# voltage_level_translators_schematic.net
KiCad netlist of a schematic drawn in Altium Designer
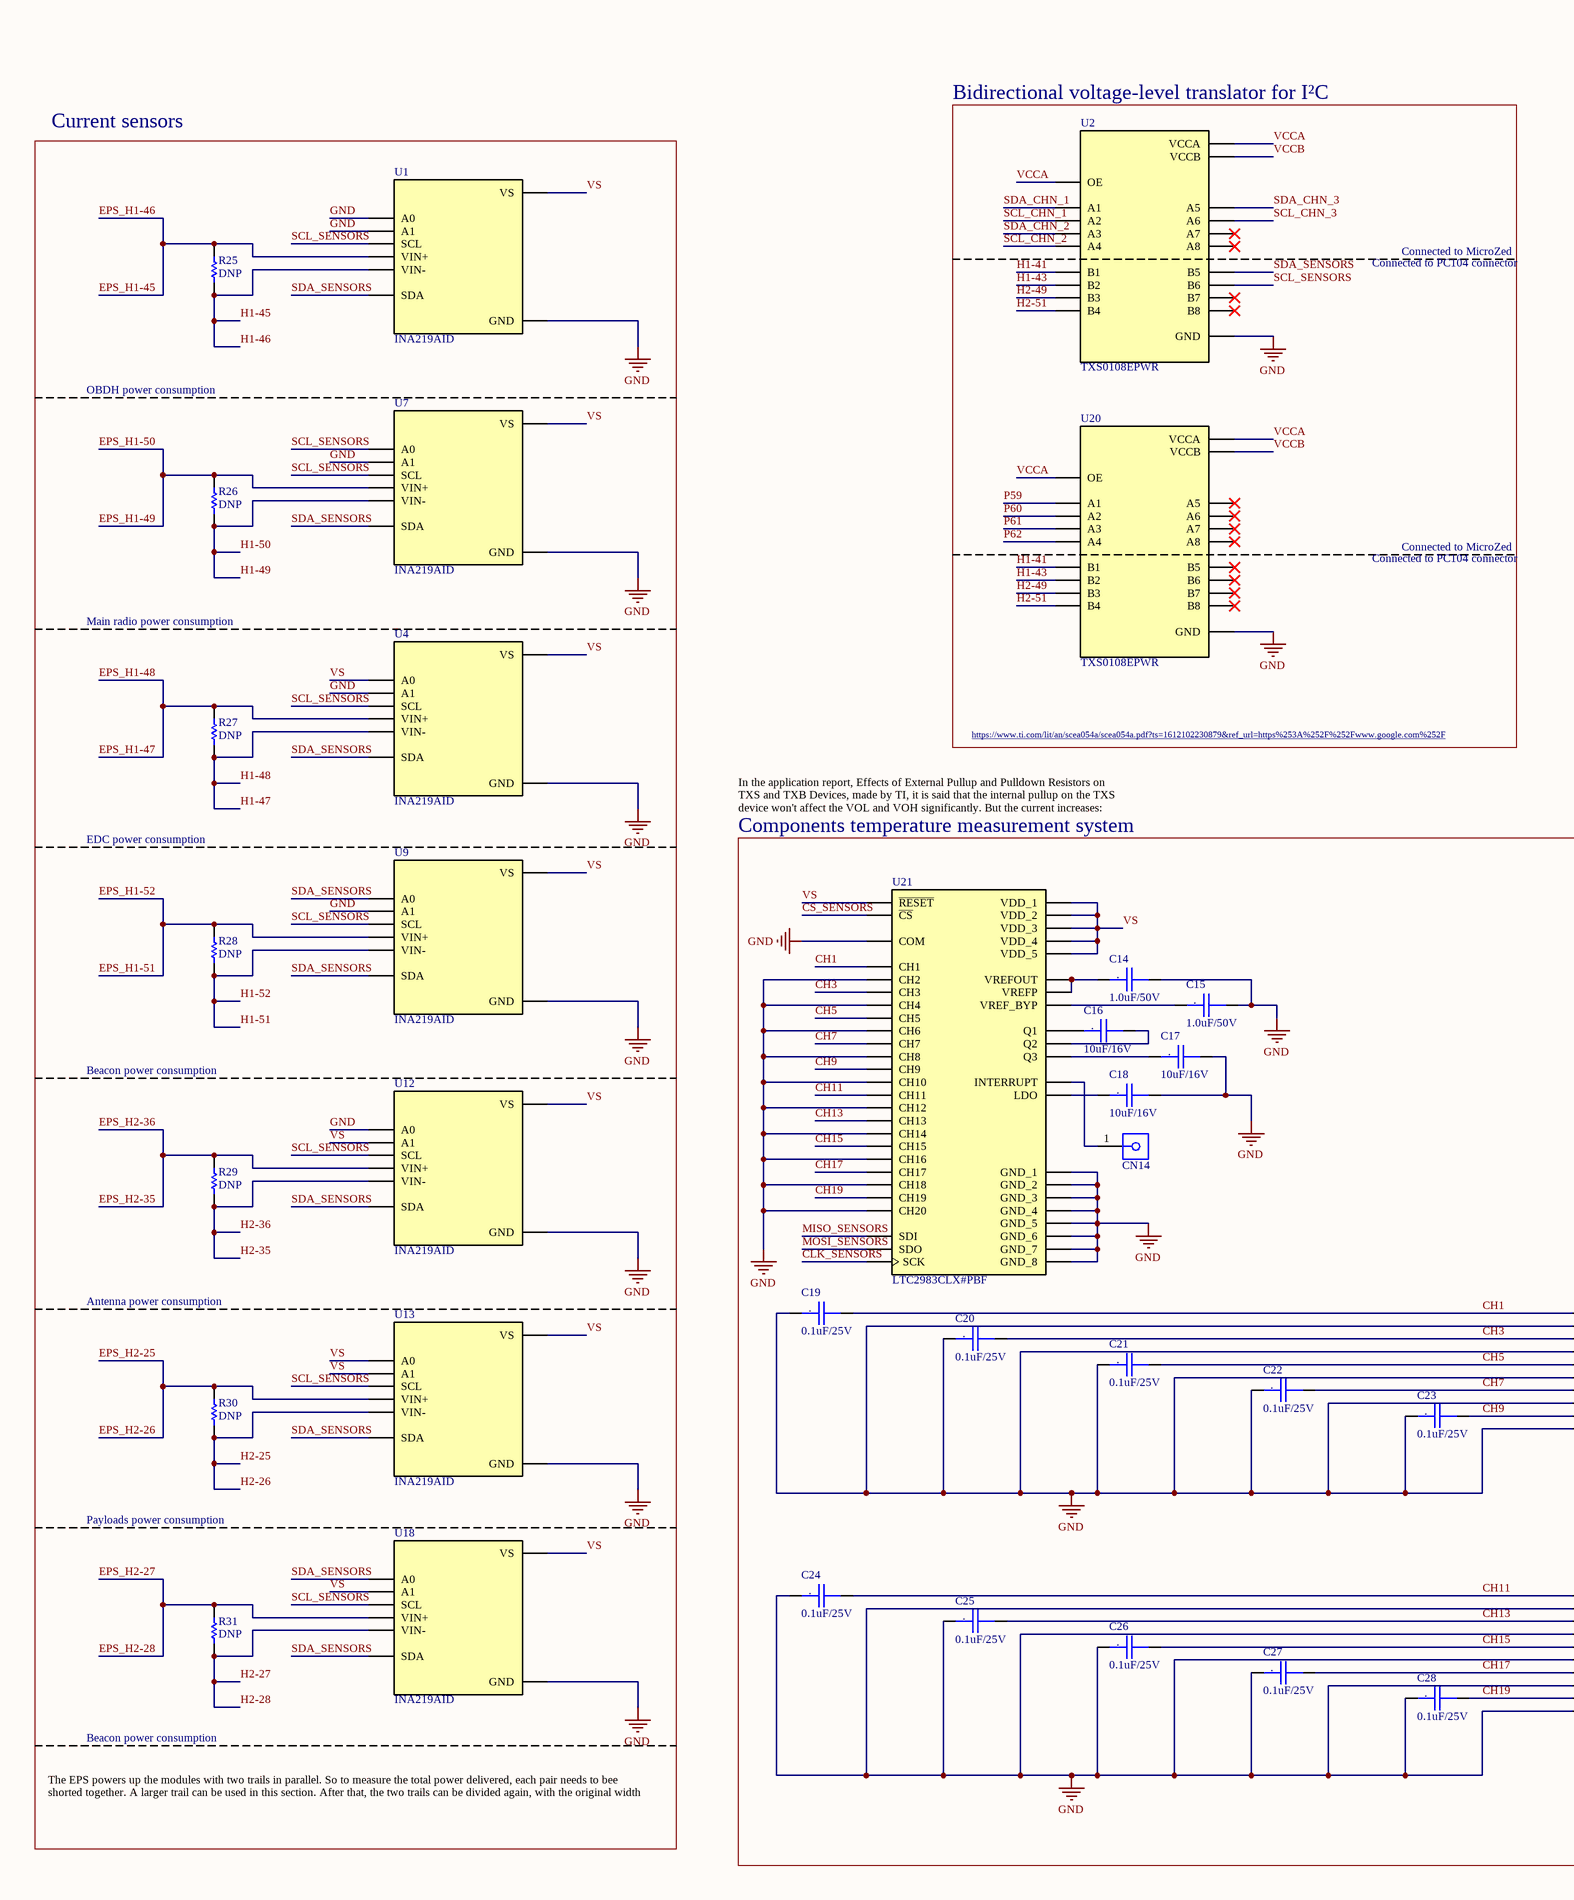
[diagram p0: voltage_level_translators_schematic.SchDoc, left]
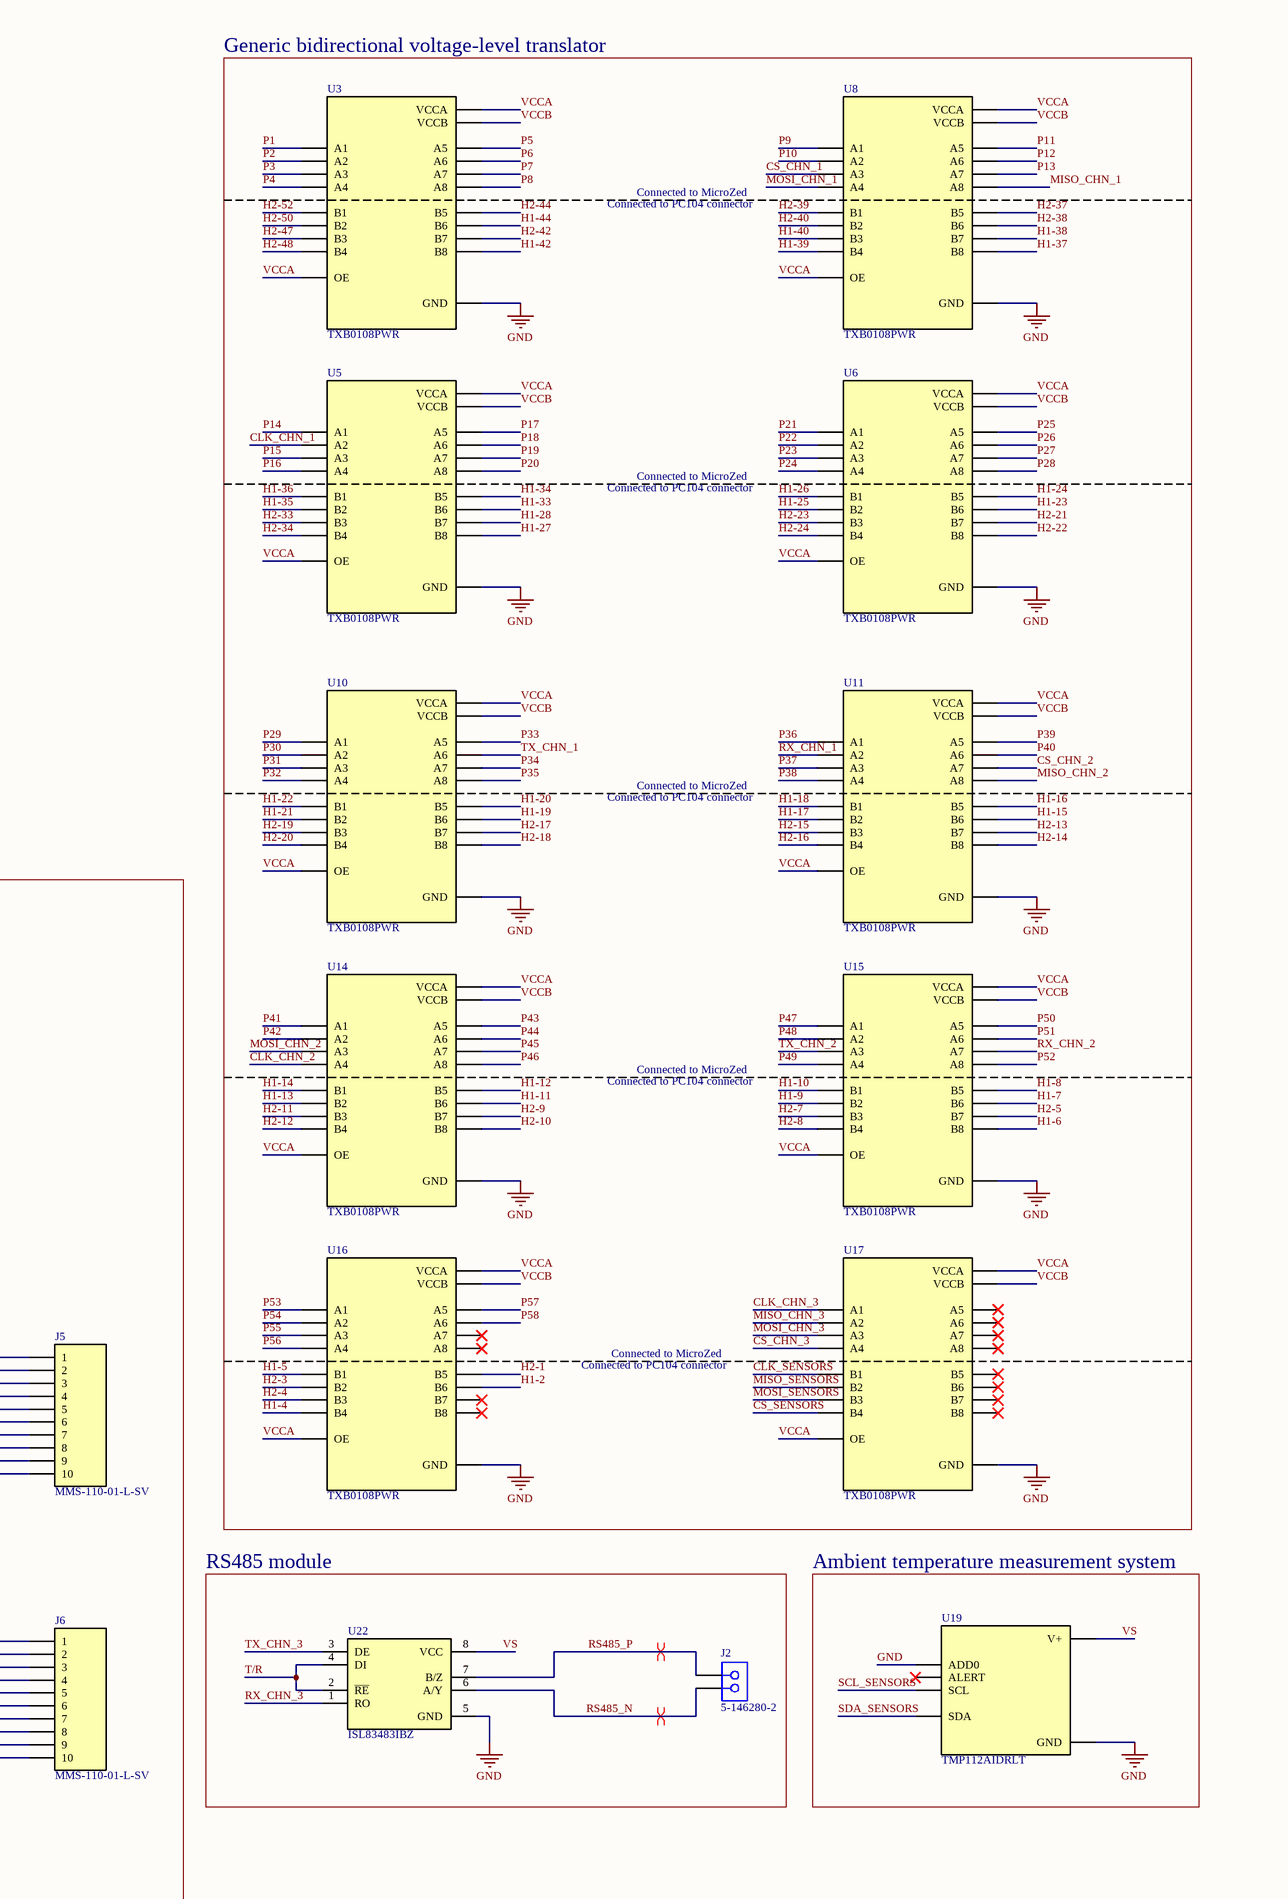
[diagram p1: voltage_level_translators_schematic.SchDoc, right]

(export (version "E")
  (design (tool "Eeschema 10.0.6"))
  (components
    (comp (ref "C14")
      (value "1.0uF/50V")
      (footprint "CC0805")
      (description "CAP CER 1.0uF 50V 10% X7R 0805")
      (fields (field (name "MANUFACTURER PART NUMBER") "C0805X105K5RACAUTO"))
      (libsource (lib "flatsat_platform_2") (part "Cap_Cer_X7R_1.0uF_50V_0805"))
    )
    (comp (ref "C15")
      (value "1.0uF/50V")
      (footprint "CC0805")
      (description "CAP CER 1.0uF 50V 10% X7R 0805")
      (fields (field (name "MANUFACTURER PART NUMBER") "C0805X105K5RACAUTO"))
      (libsource (lib "flatsat_platform_2") (part "Cap_Cer_X7R_1.0uF_50V_0805"))
    )
    (comp (ref "C16")
      (value "10uF/16V")
      (footprint "CC1210")
      (description "CAP CER 10uF 16V 10% X7R 1210")
      (fields (field (name "MANUFACTURER PART NUMBER") "C1210C106K4RACTU"))
      (libsource (lib "flatsat_platform_2") (part "Cap_Cer_X7R_10uF_16V_1210"))
    )
    (comp (ref "C17")
      (value "10uF/16V")
      (footprint "CC1210")
      (description "CAP CER 10uF 16V 10% X7R 1210")
      (fields (field (name "MANUFACTURER PART NUMBER") "C1210C106K4RACTU"))
      (libsource (lib "flatsat_platform_2") (part "Cap_Cer_X7R_10uF_16V_1210"))
    )
    (comp (ref "C18")
      (value "10uF/16V")
      (footprint "CC1210")
      (description "CAP CER 10uF 16V 10% X7R 1210")
      (fields (field (name "MANUFACTURER PART NUMBER") "C1210C106K4RACTU"))
      (libsource (lib "flatsat_platform_2") (part "Cap_Cer_X7R_10uF_16V_1210"))
    )
    (comp (ref "C19")
      (value "0.1uF/25V")
      (footprint "CC0805")
      (description "CAP CER 0.1uF 25V 10% X7R 0805")
      (fields (field (name "MANUFACTURER PART NUMBER") "CC0805KRX7R8BB104"))
      (libsource (lib "flatsat_platform_2") (part "Cap_Cer_X7R_0.1uF_25V_0805"))
    )
    (comp (ref "C20")
      (value "0.1uF/25V")
      (footprint "CC0805")
      (description "CAP CER 0.1uF 25V 10% X7R 0805")
      (fields (field (name "MANUFACTURER PART NUMBER") "CC0805KRX7R8BB104"))
      (libsource (lib "flatsat_platform_2") (part "Cap_Cer_X7R_0.1uF_25V_0805"))
    )
    (comp (ref "C21")
      (value "0.1uF/25V")
      (footprint "CC0805")
      (description "CAP CER 0.1uF 25V 10% X7R 0805")
      (fields (field (name "MANUFACTURER PART NUMBER") "CC0805KRX7R8BB104"))
      (libsource (lib "flatsat_platform_2") (part "Cap_Cer_X7R_0.1uF_25V_0805"))
    )
    (comp (ref "C22")
      (value "0.1uF/25V")
      (footprint "CC0805")
      (description "CAP CER 0.1uF 25V 10% X7R 0805")
      (fields (field (name "MANUFACTURER PART NUMBER") "CC0805KRX7R8BB104"))
      (libsource (lib "flatsat_platform_2") (part "Cap_Cer_X7R_0.1uF_25V_0805"))
    )
    (comp (ref "C23")
      (value "0.1uF/25V")
      (footprint "CC0805")
      (description "CAP CER 0.1uF 25V 10% X7R 0805")
      (fields (field (name "MANUFACTURER PART NUMBER") "CC0805KRX7R8BB104"))
      (libsource (lib "flatsat_platform_2") (part "Cap_Cer_X7R_0.1uF_25V_0805"))
    )
    (comp (ref "C24")
      (value "0.1uF/25V")
      (footprint "CC0805")
      (description "CAP CER 0.1uF 25V 10% X7R 0805")
      (fields (field (name "MANUFACTURER PART NUMBER") "CC0805KRX7R8BB104"))
      (libsource (lib "flatsat_platform_2") (part "Cap_Cer_X7R_0.1uF_25V_0805"))
    )
    (comp (ref "C25")
      (value "0.1uF/25V")
      (footprint "CC0805")
      (description "CAP CER 0.1uF 25V 10% X7R 0805")
      (fields (field (name "MANUFACTURER PART NUMBER") "CC0805KRX7R8BB104"))
      (libsource (lib "flatsat_platform_2") (part "Cap_Cer_X7R_0.1uF_25V_0805"))
    )
    (comp (ref "C26")
      (value "0.1uF/25V")
      (footprint "CC0805")
      (description "CAP CER 0.1uF 25V 10% X7R 0805")
      (fields (field (name "MANUFACTURER PART NUMBER") "CC0805KRX7R8BB104"))
      (libsource (lib "flatsat_platform_2") (part "Cap_Cer_X7R_0.1uF_25V_0805"))
    )
    (comp (ref "C27")
      (value "0.1uF/25V")
      (footprint "CC0805")
      (description "CAP CER 0.1uF 25V 10% X7R 0805")
      (fields (field (name "MANUFACTURER PART NUMBER") "CC0805KRX7R8BB104"))
      (libsource (lib "flatsat_platform_2") (part "Cap_Cer_X7R_0.1uF_25V_0805"))
    )
    (comp (ref "C28")
      (value "0.1uF/25V")
      (footprint "CC0805")
      (description "CAP CER 0.1uF 25V 10% X7R 0805")
      (fields (field (name "MANUFACTURER PART NUMBER") "CC0805KRX7R8BB104"))
      (libsource (lib "flatsat_platform_2") (part "Cap_Cer_X7R_0.1uF_25V_0805"))
    )
    (comp (ref "CN14")
      (value "TSW-101-05-T-S")
      (footprint "PIN BAR 1 2.54mm 180 GRAUS - Hide")
      (description "CONN HEADER 1POS .100\" SNGL TIN")
      (fields (field (name "MANUFACTURER") "Samtec Inc"))
      (libsource (lib "flatsat_platform_2") (part "TSW-101-05-T-S"))
    )
    (comp (ref "J2")
      (value "5-146280-2")
      (footprint "PIN BAR 2 2.54mm 180 GRAUS")
      (description "02 MODII HDR SRST B/A .100CL")
      (fields (field (name "MF") "TE Connectivity"))
      (libsource (lib "flatsat_platform_2") (part "5-146280-2"))
    )
    (comp (ref "J5")
      (value "MMS-110-01-L-SV")
      (footprint "SAMTEC_MMS-110-01-L-SV")
      (description "Conn Socket Strip SKT 10 POS 2mm Solder ST Thru-Hole Tube")
      (libsource (lib "flatsat_platform_2") (part "MMS-110-01-L-SV"))
    )
    (comp (ref "J6")
      (value "MMS-110-01-L-SV")
      (footprint "SAMTEC_MMS-110-01-L-SV")
      (description "Conn Socket Strip SKT 10 POS 2mm Solder ST Thru-Hole Tube")
      (libsource (lib "flatsat_platform_2") (part "MMS-110-01-L-SV"))
    )
    (comp (ref "R25")
      (value "DNP")
      (footprint "0805")
      (description "RES DNP 0805")
      (fields (field (name "MANUFACTURER PART NUMBER") "UR73V2ATTD47L0F"))
      (libsource (lib "flatsat_platform_2") (part "RDNP_0805"))
    )
    (comp (ref "R26")
      (value "DNP")
      (footprint "0805")
      (description "RES DNP 0805")
      (fields (field (name "MANUFACTURER PART NUMBER") "UR73V2ATTD47L0F"))
      (libsource (lib "flatsat_platform_2") (part "RDNP_0805"))
    )
    (comp (ref "R27")
      (value "DNP")
      (footprint "0805")
      (description "RES DNP 0805")
      (fields (field (name "MANUFACTURER PART NUMBER") "UR73V2ATTD47L0F"))
      (libsource (lib "flatsat_platform_2") (part "RDNP_0805"))
    )
    (comp (ref "R28")
      (value "DNP")
      (footprint "0805")
      (description "RES DNP 0805")
      (fields (field (name "MANUFACTURER PART NUMBER") "UR73V2ATTD47L0F"))
      (libsource (lib "flatsat_platform_2") (part "RDNP_0805"))
    )
    (comp (ref "R29")
      (value "DNP")
      (footprint "0805")
      (description "RES DNP 0805")
      (fields (field (name "MANUFACTURER PART NUMBER") "UR73V2ATTD47L0F"))
      (libsource (lib "flatsat_platform_2") (part "RDNP_0805"))
    )
    (comp (ref "R30")
      (value "DNP")
      (footprint "0805")
      (description "RES DNP 0805")
      (fields (field (name "MANUFACTURER PART NUMBER") "UR73V2ATTD47L0F"))
      (libsource (lib "flatsat_platform_2") (part "RDNP_0805"))
    )
    (comp (ref "R31")
      (value "DNP")
      (footprint "0805")
      (description "RES DNP 0805")
      (fields (field (name "MANUFACTURER PART NUMBER") "UR73V2ATTD47L0F"))
      (libsource (lib "flatsat_platform_2") (part "RDNP_0805"))
    )
    (comp (ref "U1")
      (value "INA219AID")
      (footprint "SOIC127P599X175-8N")
      (description "26V, 12-bit, i2c output current/voltage/power monitor 8-SOIC -40 to 125")
      (fields (field (name "MF") "Texas Instruments"))
      (libsource (lib "flatsat_platform_2") (part "INA219AID"))
    )
    (comp (ref "U2")
      (value "TXS0108EPWR")
      (footprint "SOP65P640X120-20N")
      (description "8-Bit Bidirectional Voltage-Level Shifter For Open-Drain And Push-Pull Application")
      (fields (field (name "MF") "Texas Instruments"))
      (libsource (lib "flatsat_platform_2") (part "TXS0108EPWR"))
    )
    (comp (ref "U3")
      (value "TXB0108PWR")
      (footprint "SOP65P640X120-20N")
      (fields (field (name "DIGI-KEY_PART_NUMBER") "296-21527-1-ND") (field (name "MF") "Texas Instruments"))
      (libsource (lib "flatsat_platform_2") (part "TXB0108PWR"))
    )
    (comp (ref "U4")
      (value "INA219AID")
      (footprint "SOIC127P599X175-8N")
      (description "26V, 12-bit, i2c output current/voltage/power monitor 8-SOIC -40 to 125")
      (fields (field (name "MF") "Texas Instruments"))
      (libsource (lib "flatsat_platform_2") (part "INA219AID"))
    )
    (comp (ref "U5")
      (value "TXB0108PWR")
      (footprint "SOP65P640X120-20N")
      (fields (field (name "DIGI-KEY_PART_NUMBER") "296-21527-1-ND") (field (name "MF") "Texas Instruments"))
      (libsource (lib "flatsat_platform_2") (part "TXB0108PWR"))
    )
    (comp (ref "U6")
      (value "TXB0108PWR")
      (footprint "SOP65P640X120-20N")
      (fields (field (name "DIGI-KEY_PART_NUMBER") "296-21527-1-ND") (field (name "MF") "Texas Instruments"))
      (libsource (lib "flatsat_platform_2") (part "TXB0108PWR"))
    )
    (comp (ref "U7")
      (value "INA219AID")
      (footprint "SOIC127P599X175-8N")
      (description "26V, 12-bit, i2c output current/voltage/power monitor 8-SOIC -40 to 125")
      (fields (field (name "MF") "Texas Instruments"))
      (libsource (lib "flatsat_platform_2") (part "INA219AID"))
    )
    (comp (ref "U8")
      (value "TXB0108PWR")
      (footprint "SOP65P640X120-20N")
      (fields (field (name "DIGI-KEY_PART_NUMBER") "296-21527-1-ND") (field (name "MF") "Texas Instruments"))
      (libsource (lib "flatsat_platform_2") (part "TXB0108PWR"))
    )
    (comp (ref "U9")
      (value "INA219AID")
      (footprint "SOIC127P599X175-8N")
      (description "26V, 12-bit, i2c output current/voltage/power monitor 8-SOIC -40 to 125")
      (fields (field (name "MF") "Texas Instruments"))
      (libsource (lib "flatsat_platform_2") (part "INA219AID"))
    )
    (comp (ref "U10")
      (value "TXB0108PWR")
      (footprint "SOP65P640X120-20N")
      (fields (field (name "DIGI-KEY_PART_NUMBER") "296-21527-1-ND") (field (name "MF") "Texas Instruments"))
      (libsource (lib "flatsat_platform_2") (part "TXB0108PWR"))
    )
    (comp (ref "U11")
      (value "TXB0108PWR")
      (footprint "SOP65P640X120-20N")
      (fields (field (name "DIGI-KEY_PART_NUMBER") "296-21527-1-ND") (field (name "MF") "Texas Instruments"))
      (libsource (lib "flatsat_platform_2") (part "TXB0108PWR"))
    )
    (comp (ref "U12")
      (value "INA219AID")
      (footprint "SOIC127P599X175-8N")
      (description "26V, 12-bit, i2c output current/voltage/power monitor 8-SOIC -40 to 125")
      (fields (field (name "MF") "Texas Instruments"))
      (libsource (lib "flatsat_platform_2") (part "INA219AID"))
    )
    (comp (ref "U13")
      (value "INA219AID")
      (footprint "SOIC127P599X175-8N")
      (description "26V, 12-bit, i2c output current/voltage/power monitor 8-SOIC -40 to 125")
      (fields (field (name "MF") "Texas Instruments"))
      (libsource (lib "flatsat_platform_2") (part "INA219AID"))
    )
    (comp (ref "U14")
      (value "TXB0108PWR")
      (footprint "SOP65P640X120-20N")
      (fields (field (name "DIGI-KEY_PART_NUMBER") "296-21527-1-ND") (field (name "MF") "Texas Instruments"))
      (libsource (lib "flatsat_platform_2") (part "TXB0108PWR"))
    )
    (comp (ref "U15")
      (value "TXB0108PWR")
      (footprint "SOP65P640X120-20N")
      (fields (field (name "DIGI-KEY_PART_NUMBER") "296-21527-1-ND") (field (name "MF") "Texas Instruments"))
      (libsource (lib "flatsat_platform_2") (part "TXB0108PWR"))
    )
    (comp (ref "U16")
      (value "TXB0108PWR")
      (footprint "SOP65P640X120-20N")
      (fields (field (name "DIGI-KEY_PART_NUMBER") "296-21527-1-ND") (field (name "MF") "Texas Instruments"))
      (libsource (lib "flatsat_platform_2") (part "TXB0108PWR"))
    )
    (comp (ref "U17")
      (value "TXB0108PWR")
      (footprint "SOP65P640X120-20N")
      (fields (field (name "DIGI-KEY_PART_NUMBER") "296-21527-1-ND") (field (name "MF") "Texas Instruments"))
      (libsource (lib "flatsat_platform_2") (part "TXB0108PWR"))
    )
    (comp (ref "U18")
      (value "INA219AID")
      (footprint "SOIC127P599X175-8N")
      (description "26V, 12-bit, i2c output current/voltage/power monitor 8-SOIC -40 to 125")
      (fields (field (name "MF") "Texas Instruments"))
      (libsource (lib "flatsat_platform_2") (part "INA219AID"))
    )
    (comp (ref "U19")
      (value "TMP112AIDRLT")
      (footprint "SOT50P160X60-6N")
      (fields (field (name "MF") "Texas Instruments"))
      (libsource (lib "flatsat_platform_2") (part "TMP112AIDRLT"))
    )
    (comp (ref "U20")
      (value "TXS0108EPWR")
      (footprint "SOP65P640X120-20N")
      (description "8-Bit Bidirectional Voltage-Level Shifter For Open-Drain And Push-Pull Application")
      (fields (field (name "MF") "Texas Instruments"))
      (libsource (lib "flatsat_platform_2") (part "TXS0108EPWR"))
    )
    (comp (ref "U21")
      (value "LTC2983CLX#PBF")
      (footprint "QFP50P900X900X160-48N")
      (description "IC SENSOR THERMAL")
      (fields (field (name "MF") "Analog Devices"))
      (libsource (lib "flatsat_platform_2") (part "LTC2983CLX#PBF"))
    )
    (comp (ref "U22")
      (value "ISL83483IBZ")
      (footprint "SOIC127P600X175-8N")
      (description "1/1 Transceiver Half RS422, RS485 8-SOIC")
      (fields
        (field (name "MF") "Renesas Electronics")
        (field (name "MANUFACTURER PART NUMBER") "ISL83483IBZ-T")
      )
      (libsource (lib "flatsat_platform_2") (part "ISL83483IBZ"))
    )
  )
  (nets
    (net (code "1") (name "/CH1") (class "Default")
      (node (ref "C19") (pin "2") (pinfunction "2_2") (pintype "passive"))
      (node (ref "J5") (pin "1") (pinfunction "1_1") (pintype "passive"))
      (node (ref "U21") (pin "16") (pinfunction "CH1_16") (pintype "power_in"))
    )
    (net (code "2") (name "/CH3") (class "Default")
      (node (ref "C20") (pin "2") (pinfunction "2_2") (pintype "passive"))
      (node (ref "J5") (pin "3") (pinfunction "3_3") (pintype "passive"))
      (node (ref "U21") (pin "18") (pinfunction "CH3_18") (pintype "power_in"))
    )
    (net (code "3") (name "/CH5") (class "Default")
      (node (ref "C21") (pin "2") (pinfunction "2_2") (pintype "passive"))
      (node (ref "J5") (pin "5") (pinfunction "5_5") (pintype "passive"))
      (node (ref "U21") (pin "20") (pinfunction "CH5_20") (pintype "power_in"))
    )
    (net (code "4") (name "/CH7") (class "Default")
      (node (ref "C22") (pin "2") (pinfunction "2_2") (pintype "passive"))
      (node (ref "J5") (pin "7") (pinfunction "7_7") (pintype "passive"))
      (node (ref "U21") (pin "22") (pinfunction "CH7_22") (pintype "power_in"))
    )
    (net (code "5") (name "/CH9") (class "Default")
      (node (ref "C23") (pin "2") (pinfunction "2_2") (pintype "passive"))
      (node (ref "J5") (pin "9") (pinfunction "9_9") (pintype "passive"))
      (node (ref "U21") (pin "24") (pinfunction "CH9_24") (pintype "power_in"))
    )
    (net (code "6") (name "/CH11") (class "Default")
      (node (ref "C24") (pin "2") (pinfunction "2_2") (pintype "passive"))
      (node (ref "J6") (pin "1") (pinfunction "1_1") (pintype "passive"))
      (node (ref "U21") (pin "26") (pinfunction "CH11_26") (pintype "power_in"))
    )
    (net (code "7") (name "/CH13") (class "Default")
      (node (ref "C25") (pin "2") (pinfunction "2_2") (pintype "passive"))
      (node (ref "J6") (pin "3") (pinfunction "3_3") (pintype "passive"))
      (node (ref "U21") (pin "28") (pinfunction "CH13_28") (pintype "power_in"))
    )
    (net (code "8") (name "/CH15") (class "Default")
      (node (ref "C26") (pin "2") (pinfunction "2_2") (pintype "passive"))
      (node (ref "J6") (pin "5") (pinfunction "5_5") (pintype "passive"))
      (node (ref "U21") (pin "30") (pinfunction "CH15_30") (pintype "power_in"))
    )
    (net (code "9") (name "/CH17") (class "Default")
      (node (ref "C27") (pin "2") (pinfunction "2_2") (pintype "passive"))
      (node (ref "J6") (pin "7") (pinfunction "7_7") (pintype "passive"))
      (node (ref "U21") (pin "32") (pinfunction "CH17_32") (pintype "power_in"))
    )
    (net (code "10") (name "/CH19") (class "Default")
      (node (ref "C28") (pin "2") (pinfunction "2_2") (pintype "passive"))
      (node (ref "J6") (pin "9") (pinfunction "9_9") (pintype "passive"))
      (node (ref "U21") (pin "34") (pinfunction "CH19_34") (pintype "power_in"))
    )
    (net (code "11") (name "/CLK_CHN_1") (class "Default")
      (node (ref "U5") (pin "3") (pinfunction "A2_3") (pintype "power_in"))
    )
    (net (code "12") (name "/CLK_CHN_2") (class "Default")
      (node (ref "U14") (pin "5") (pinfunction "A4_5") (pintype "power_in"))
    )
    (net (code "13") (name "/CLK_CHN_3") (class "Default")
      (node (ref "U17") (pin "1") (pinfunction "A1_1") (pintype "power_in"))
    )
    (net (code "14") (name "/CLK_SENSORS") (class "Default")
      (node (ref "U17") (pin "20") (pinfunction "B1_20") (pintype "power_in"))
      (node (ref "U21") (pin "38") (pinfunction "SCK_38") (pintype "power_in"))
    )
    (net (code "15") (name "/CS_CHN_1") (class "Default")
      (node (ref "U8") (pin "4") (pinfunction "A3_4") (pintype "power_in"))
    )
    (net (code "16") (name "/CS_CHN_2") (class "Default")
      (node (ref "U11") (pin "8") (pinfunction "A7_8") (pintype "power_in"))
    )
    (net (code "17") (name "/CS_CHN_3") (class "Default")
      (node (ref "U17") (pin "5") (pinfunction "A4_5") (pintype "power_in"))
    )
    (net (code "18") (name "/CS_SENSORS") (class "Default")
      (node (ref "U17") (pin "16") (pinfunction "B4_16") (pintype "power_in"))
      (node (ref "U21") (pin "41") (pinfunction "~{CS}_41") (pintype "power_in"))
    )
    (net (code "19") (name "/EPS_H1-45") (class "Default")
      (node (ref "R25") (pin "1") (pinfunction "1_1") (pintype "passive"))
      (node (ref "U1") (pin "8") (pinfunction "VIN+_8") (pintype "power_in"))
    )
    (net (code "20") (name "/EPS_H1-47") (class "Default")
      (node (ref "R27") (pin "1") (pinfunction "1_1") (pintype "passive"))
      (node (ref "U4") (pin "8") (pinfunction "VIN+_8") (pintype "power_in"))
    )
    (net (code "21") (name "/EPS_H1-49") (class "Default")
      (node (ref "R26") (pin "1") (pinfunction "1_1") (pintype "passive"))
      (node (ref "U7") (pin "8") (pinfunction "VIN+_8") (pintype "power_in"))
    )
    (net (code "22") (name "/EPS_H1-51") (class "Default")
      (node (ref "R28") (pin "1") (pinfunction "1_1") (pintype "passive"))
      (node (ref "U9") (pin "8") (pinfunction "VIN+_8") (pintype "power_in"))
    )
    (net (code "23") (name "/EPS_H2-25") (class "Default")
      (node (ref "R30") (pin "1") (pinfunction "1_1") (pintype "passive"))
      (node (ref "U13") (pin "8") (pinfunction "VIN+_8") (pintype "power_in"))
    )
    (net (code "24") (name "/EPS_H2-27") (class "Default")
      (node (ref "R31") (pin "1") (pinfunction "1_1") (pintype "passive"))
      (node (ref "U18") (pin "8") (pinfunction "VIN+_8") (pintype "power_in"))
    )
    (net (code "25") (name "/EPS_H2-35") (class "Default")
      (node (ref "R29") (pin "1") (pinfunction "1_1") (pintype "passive"))
      (node (ref "U12") (pin "8") (pinfunction "VIN+_8") (pintype "power_in"))
    )
    (net (code "26") (name "/H1-2") (class "Default")
      (node (ref "U16") (pin "14") (pinfunction "B6_14") (pintype "power_in"))
    )
    (net (code "27") (name "/H1-4") (class "Default")
      (node (ref "U16") (pin "16") (pinfunction "B4_16") (pintype "power_in"))
    )
    (net (code "28") (name "/H1-5") (class "Default")
      (node (ref "U16") (pin "20") (pinfunction "B1_20") (pintype "power_in"))
    )
    (net (code "29") (name "/H1-6") (class "Default")
      (node (ref "U15") (pin "12") (pinfunction "B8_12") (pintype "power_in"))
    )
    (net (code "30") (name "/H1-7") (class "Default")
      (node (ref "U15") (pin "14") (pinfunction "B6_14") (pintype "power_in"))
    )
    (net (code "31") (name "/H1-8") (class "Default")
      (node (ref "U15") (pin "15") (pinfunction "B5_15") (pintype "power_in"))
    )
    (net (code "32") (name "/H1-9") (class "Default")
      (node (ref "U15") (pin "18") (pinfunction "B2_18") (pintype "power_in"))
    )
    (net (code "33") (name "/H1-10") (class "Default")
      (node (ref "U15") (pin "20") (pinfunction "B1_20") (pintype "power_in"))
    )
    (net (code "34") (name "/H1-11") (class "Default")
      (node (ref "U14") (pin "14") (pinfunction "B6_14") (pintype "power_in"))
    )
    (net (code "35") (name "/H1-12") (class "Default")
      (node (ref "U14") (pin "15") (pinfunction "B5_15") (pintype "power_in"))
    )
    (net (code "36") (name "/H1-13") (class "Default")
      (node (ref "U14") (pin "18") (pinfunction "B2_18") (pintype "power_in"))
    )
    (net (code "37") (name "/H1-14") (class "Default")
      (node (ref "U14") (pin "20") (pinfunction "B1_20") (pintype "power_in"))
    )
    (net (code "38") (name "/H1-15") (class "Default")
      (node (ref "U11") (pin "14") (pinfunction "B6_14") (pintype "power_in"))
    )
    (net (code "39") (name "/H1-16") (class "Default")
      (node (ref "U11") (pin "15") (pinfunction "B5_15") (pintype "power_in"))
    )
    (net (code "40") (name "/H1-17") (class "Default")
      (node (ref "U11") (pin "18") (pinfunction "B2_18") (pintype "power_in"))
    )
    (net (code "41") (name "/H1-18") (class "Default")
      (node (ref "U11") (pin "20") (pinfunction "B1_20") (pintype "power_in"))
    )
    (net (code "42") (name "/H1-19") (class "Default")
      (node (ref "U10") (pin "14") (pinfunction "B6_14") (pintype "power_in"))
    )
    (net (code "43") (name "/H1-20") (class "Default")
      (node (ref "U10") (pin "15") (pinfunction "B5_15") (pintype "power_in"))
    )
    (net (code "44") (name "/H1-21") (class "Default")
      (node (ref "U10") (pin "18") (pinfunction "B2_18") (pintype "power_in"))
    )
    (net (code "45") (name "/H1-22") (class "Default")
      (node (ref "U10") (pin "20") (pinfunction "B1_20") (pintype "power_in"))
    )
    (net (code "46") (name "/H1-23") (class "Default")
      (node (ref "U6") (pin "14") (pinfunction "B6_14") (pintype "power_in"))
    )
    (net (code "47") (name "/H1-24") (class "Default")
      (node (ref "U6") (pin "15") (pinfunction "B5_15") (pintype "power_in"))
    )
    (net (code "48") (name "/H1-25") (class "Default")
      (node (ref "U6") (pin "18") (pinfunction "B2_18") (pintype "power_in"))
    )
    (net (code "49") (name "/H1-26") (class "Default")
      (node (ref "U6") (pin "20") (pinfunction "B1_20") (pintype "power_in"))
    )
    (net (code "50") (name "/H1-27") (class "Default")
      (node (ref "U5") (pin "12") (pinfunction "B8_12") (pintype "power_in"))
    )
    (net (code "51") (name "/H1-28") (class "Default")
      (node (ref "U5") (pin "13") (pinfunction "B7_13") (pintype "power_in"))
    )
    (net (code "52") (name "/H1-33") (class "Default")
      (node (ref "U5") (pin "14") (pinfunction "B6_14") (pintype "power_in"))
    )
    (net (code "53") (name "/H1-34") (class "Default")
      (node (ref "U5") (pin "15") (pinfunction "B5_15") (pintype "power_in"))
    )
    (net (code "54") (name "/H1-35") (class "Default")
      (node (ref "U5") (pin "18") (pinfunction "B2_18") (pintype "power_in"))
    )
    (net (code "55") (name "/H1-36") (class "Default")
      (node (ref "U5") (pin "20") (pinfunction "B1_20") (pintype "power_in"))
    )
    (net (code "56") (name "/H1-37") (class "Default")
      (node (ref "U8") (pin "12") (pinfunction "B8_12") (pintype "power_in"))
    )
    (net (code "57") (name "/H1-38") (class "Default")
      (node (ref "U8") (pin "13") (pinfunction "B7_13") (pintype "power_in"))
    )
    (net (code "58") (name "/H1-39") (class "Default")
      (node (ref "U8") (pin "16") (pinfunction "B4_16") (pintype "power_in"))
    )
    (net (code "59") (name "/H1-40") (class "Default")
      (node (ref "U8") (pin "17") (pinfunction "B3_17") (pintype "power_in"))
    )
    (net (code "60") (name "/H1-41") (class "Default")
      (node (ref "U2") (pin "20") (pinfunction "B1_20") (pintype "power_in"))
      (node (ref "U20") (pin "20") (pinfunction "B1_20") (pintype "power_in"))
    )
    (net (code "61") (name "/H1-42") (class "Default")
      (node (ref "U3") (pin "12") (pinfunction "B8_12") (pintype "power_in"))
    )
    (net (code "62") (name "/H1-43") (class "Default")
      (node (ref "U2") (pin "18") (pinfunction "B2_18") (pintype "power_in"))
      (node (ref "U20") (pin "18") (pinfunction "B2_18") (pintype "power_in"))
    )
    (net (code "63") (name "/H1-44") (class "Default")
      (node (ref "U3") (pin "14") (pinfunction "B6_14") (pintype "power_in"))
    )
    (net (code "64") (name "/H1-45") (class "Default")
      (node (ref "R25") (pin "2") (pinfunction "2_2") (pintype "passive"))
      (node (ref "U1") (pin "7") (pinfunction "VIN-_7") (pintype "power_in"))
    )
    (net (code "65") (name "/H1-47") (class "Default")
      (node (ref "R27") (pin "2") (pinfunction "2_2") (pintype "passive"))
      (node (ref "U4") (pin "7") (pinfunction "VIN-_7") (pintype "power_in"))
    )
    (net (code "66") (name "/H1-49") (class "Default")
      (node (ref "R26") (pin "2") (pinfunction "2_2") (pintype "passive"))
      (node (ref "U7") (pin "7") (pinfunction "VIN-_7") (pintype "power_in"))
    )
    (net (code "67") (name "/H1-51") (class "Default")
      (node (ref "R28") (pin "2") (pinfunction "2_2") (pintype "passive"))
      (node (ref "U9") (pin "7") (pinfunction "VIN-_7") (pintype "power_in"))
    )
    (net (code "68") (name "/H2-1") (class "Default")
      (node (ref "U16") (pin "15") (pinfunction "B5_15") (pintype "power_in"))
    )
    (net (code "69") (name "/H2-3") (class "Default")
      (node (ref "U16") (pin "18") (pinfunction "B2_18") (pintype "power_in"))
    )
    (net (code "70") (name "/H2-4") (class "Default")
      (node (ref "U16") (pin "17") (pinfunction "B3_17") (pintype "power_in"))
    )
    (net (code "71") (name "/H2-5") (class "Default")
      (node (ref "U15") (pin "13") (pinfunction "B7_13") (pintype "power_in"))
    )
    (net (code "72") (name "/H2-7") (class "Default")
      (node (ref "U15") (pin "17") (pinfunction "B3_17") (pintype "power_in"))
    )
    (net (code "73") (name "/H2-8") (class "Default")
      (node (ref "U15") (pin "16") (pinfunction "B4_16") (pintype "power_in"))
    )
    (net (code "74") (name "/H2-9") (class "Default")
      (node (ref "U14") (pin "13") (pinfunction "B7_13") (pintype "power_in"))
    )
    (net (code "75") (name "/H2-10") (class "Default")
      (node (ref "U14") (pin "12") (pinfunction "B8_12") (pintype "power_in"))
    )
    (net (code "76") (name "/H2-11") (class "Default")
      (node (ref "U14") (pin "17") (pinfunction "B3_17") (pintype "power_in"))
    )
    (net (code "77") (name "/H2-12") (class "Default")
      (node (ref "U14") (pin "16") (pinfunction "B4_16") (pintype "power_in"))
    )
    (net (code "78") (name "/H2-13") (class "Default")
      (node (ref "U11") (pin "13") (pinfunction "B7_13") (pintype "power_in"))
    )
    (net (code "79") (name "/H2-14") (class "Default")
      (node (ref "U11") (pin "12") (pinfunction "B8_12") (pintype "power_in"))
    )
    (net (code "80") (name "/H2-15") (class "Default")
      (node (ref "U11") (pin "17") (pinfunction "B3_17") (pintype "power_in"))
    )
    (net (code "81") (name "/H2-16") (class "Default")
      (node (ref "U11") (pin "16") (pinfunction "B4_16") (pintype "power_in"))
    )
    (net (code "82") (name "/H2-17") (class "Default")
      (node (ref "U10") (pin "13") (pinfunction "B7_13") (pintype "power_in"))
    )
    (net (code "83") (name "/H2-18") (class "Default")
      (node (ref "U10") (pin "12") (pinfunction "B8_12") (pintype "power_in"))
    )
    (net (code "84") (name "/H2-19") (class "Default")
      (node (ref "U10") (pin "17") (pinfunction "B3_17") (pintype "power_in"))
    )
    (net (code "85") (name "/H2-20") (class "Default")
      (node (ref "U10") (pin "16") (pinfunction "B4_16") (pintype "power_in"))
    )
    (net (code "86") (name "/H2-21") (class "Default")
      (node (ref "U6") (pin "13") (pinfunction "B7_13") (pintype "power_in"))
    )
    (net (code "87") (name "/H2-22") (class "Default")
      (node (ref "U6") (pin "12") (pinfunction "B8_12") (pintype "power_in"))
    )
    (net (code "88") (name "/H2-23") (class "Default")
      (node (ref "U6") (pin "17") (pinfunction "B3_17") (pintype "power_in"))
    )
    (net (code "89") (name "/H2-24") (class "Default")
      (node (ref "U6") (pin "16") (pinfunction "B4_16") (pintype "power_in"))
    )
    (net (code "90") (name "/H2-25") (class "Default")
      (node (ref "R30") (pin "2") (pinfunction "2_2") (pintype "passive"))
      (node (ref "U13") (pin "7") (pinfunction "VIN-_7") (pintype "power_in"))
    )
    (net (code "91") (name "/H2-27") (class "Default")
      (node (ref "R31") (pin "2") (pinfunction "2_2") (pintype "passive"))
      (node (ref "U18") (pin "7") (pinfunction "VIN-_7") (pintype "power_in"))
    )
    (net (code "92") (name "/H2-33") (class "Default")
      (node (ref "U5") (pin "17") (pinfunction "B3_17") (pintype "power_in"))
    )
    (net (code "93") (name "/H2-34") (class "Default")
      (node (ref "U5") (pin "16") (pinfunction "B4_16") (pintype "power_in"))
    )
    (net (code "94") (name "/H2-35") (class "Default")
      (node (ref "R29") (pin "2") (pinfunction "2_2") (pintype "passive"))
      (node (ref "U12") (pin "7") (pinfunction "VIN-_7") (pintype "power_in"))
    )
    (net (code "95") (name "/H2-37") (class "Default")
      (node (ref "U8") (pin "15") (pinfunction "B5_15") (pintype "power_in"))
    )
    (net (code "96") (name "/H2-38") (class "Default")
      (node (ref "U8") (pin "14") (pinfunction "B6_14") (pintype "power_in"))
    )
    (net (code "97") (name "/H2-39") (class "Default")
      (node (ref "U8") (pin "20") (pinfunction "B1_20") (pintype "power_in"))
    )
    (net (code "98") (name "/H2-40") (class "Default")
      (node (ref "U8") (pin "18") (pinfunction "B2_18") (pintype "power_in"))
    )
    (net (code "99") (name "/H2-42") (class "Default")
      (node (ref "U3") (pin "13") (pinfunction "B7_13") (pintype "power_in"))
    )
    (net (code "100") (name "/H2-44") (class "Default")
      (node (ref "U3") (pin "15") (pinfunction "B5_15") (pintype "power_in"))
    )
    (net (code "101") (name "/H2-47") (class "Default")
      (node (ref "U3") (pin "17") (pinfunction "B3_17") (pintype "power_in"))
    )
    (net (code "102") (name "/H2-48") (class "Default")
      (node (ref "U3") (pin "16") (pinfunction "B4_16") (pintype "power_in"))
    )
    (net (code "103") (name "/H2-49") (class "Default")
      (node (ref "U2") (pin "17") (pinfunction "B3_17") (pintype "power_in"))
      (node (ref "U20") (pin "17") (pinfunction "B3_17") (pintype "power_in"))
    )
    (net (code "104") (name "/H2-50") (class "Default")
      (node (ref "U3") (pin "18") (pinfunction "B2_18") (pintype "power_in"))
    )
    (net (code "105") (name "/H2-51") (class "Default")
      (node (ref "U2") (pin "16") (pinfunction "B4_16") (pintype "power_in"))
      (node (ref "U20") (pin "16") (pinfunction "B4_16") (pintype "power_in"))
    )
    (net (code "106") (name "/H2-52") (class "Default")
      (node (ref "U3") (pin "20") (pinfunction "B1_20") (pintype "power_in"))
    )
    (net (code "107") (name "/MISO_CHN_1") (class "Default")
      (node (ref "U8") (pin "9") (pinfunction "A8_9") (pintype "power_in"))
    )
    (net (code "108") (name "/MISO_CHN_2") (class "Default")
      (node (ref "U11") (pin "9") (pinfunction "A8_9") (pintype "power_in"))
    )
    (net (code "109") (name "/MISO_CHN_3") (class "Default")
      (node (ref "U17") (pin "3") (pinfunction "A2_3") (pintype "power_in"))
    )
    (net (code "110") (name "/MISO_SENSORS") (class "Default")
      (node (ref "U17") (pin "18") (pinfunction "B2_18") (pintype "power_in"))
      (node (ref "U21") (pin "40") (pinfunction "SDI_40") (pintype "power_in"))
    )
    (net (code "111") (name "/MOSI_CHN_1") (class "Default")
      (node (ref "U8") (pin "5") (pinfunction "A4_5") (pintype "power_in"))
    )
    (net (code "112") (name "/MOSI_CHN_2") (class "Default")
      (node (ref "U14") (pin "4") (pinfunction "A3_4") (pintype "power_in"))
    )
    (net (code "113") (name "/MOSI_CHN_3") (class "Default")
      (node (ref "U17") (pin "4") (pinfunction "A3_4") (pintype "power_in"))
    )
    (net (code "114") (name "/MOSI_SENSORS") (class "Default")
      (node (ref "U17") (pin "17") (pinfunction "B3_17") (pintype "power_in"))
      (node (ref "U21") (pin "39") (pinfunction "SDO_39") (pintype "power_in"))
    )
    (net (code "115") (name "/P1") (class "Default")
      (node (ref "U3") (pin "1") (pinfunction "A1_1") (pintype "power_in"))
    )
    (net (code "116") (name "/P2") (class "Default")
      (node (ref "U3") (pin "3") (pinfunction "A2_3") (pintype "power_in"))
    )
    (net (code "117") (name "/P3") (class "Default")
      (node (ref "U3") (pin "4") (pinfunction "A3_4") (pintype "power_in"))
    )
    (net (code "118") (name "/P4") (class "Default")
      (node (ref "U3") (pin "5") (pinfunction "A4_5") (pintype "power_in"))
    )
    (net (code "119") (name "/P5") (class "Default")
      (node (ref "U3") (pin "6") (pinfunction "A5_6") (pintype "power_in"))
    )
    (net (code "120") (name "/P6") (class "Default")
      (node (ref "U3") (pin "7") (pinfunction "A6_7") (pintype "power_in"))
    )
    (net (code "121") (name "/P7") (class "Default")
      (node (ref "U3") (pin "8") (pinfunction "A7_8") (pintype "power_in"))
    )
    (net (code "122") (name "/P8") (class "Default")
      (node (ref "U3") (pin "9") (pinfunction "A8_9") (pintype "power_in"))
    )
    (net (code "123") (name "/P9") (class "Default")
      (node (ref "U8") (pin "1") (pinfunction "A1_1") (pintype "power_in"))
    )
    (net (code "124") (name "/P10") (class "Default")
      (node (ref "U8") (pin "3") (pinfunction "A2_3") (pintype "power_in"))
    )
    (net (code "125") (name "/P11") (class "Default")
      (node (ref "U8") (pin "6") (pinfunction "A5_6") (pintype "power_in"))
    )
    (net (code "126") (name "/P12") (class "Default")
      (node (ref "U8") (pin "7") (pinfunction "A6_7") (pintype "power_in"))
    )
    (net (code "127") (name "/P13") (class "Default")
      (node (ref "U8") (pin "8") (pinfunction "A7_8") (pintype "power_in"))
    )
    (net (code "128") (name "/P14") (class "Default")
      (node (ref "U5") (pin "1") (pinfunction "A1_1") (pintype "power_in"))
    )
    (net (code "129") (name "/P15") (class "Default")
      (node (ref "U5") (pin "4") (pinfunction "A3_4") (pintype "power_in"))
    )
    (net (code "130") (name "/P16") (class "Default")
      (node (ref "U5") (pin "5") (pinfunction "A4_5") (pintype "power_in"))
    )
    (net (code "131") (name "/P17") (class "Default")
      (node (ref "U5") (pin "6") (pinfunction "A5_6") (pintype "power_in"))
    )
    (net (code "132") (name "/P18") (class "Default")
      (node (ref "U5") (pin "7") (pinfunction "A6_7") (pintype "power_in"))
    )
    (net (code "133") (name "/P19") (class "Default")
      (node (ref "U5") (pin "8") (pinfunction "A7_8") (pintype "power_in"))
    )
    (net (code "134") (name "/P20") (class "Default")
      (node (ref "U5") (pin "9") (pinfunction "A8_9") (pintype "power_in"))
    )
    (net (code "135") (name "/P21") (class "Default")
      (node (ref "U6") (pin "1") (pinfunction "A1_1") (pintype "power_in"))
    )
    (net (code "136") (name "/P22") (class "Default")
      (node (ref "U6") (pin "3") (pinfunction "A2_3") (pintype "power_in"))
    )
    (net (code "137") (name "/P23") (class "Default")
      (node (ref "U6") (pin "4") (pinfunction "A3_4") (pintype "power_in"))
    )
    (net (code "138") (name "/P24") (class "Default")
      (node (ref "U6") (pin "5") (pinfunction "A4_5") (pintype "power_in"))
    )
    (net (code "139") (name "/P25") (class "Default")
      (node (ref "U6") (pin "6") (pinfunction "A5_6") (pintype "power_in"))
    )
    (net (code "140") (name "/P26") (class "Default")
      (node (ref "U6") (pin "7") (pinfunction "A6_7") (pintype "power_in"))
    )
    (net (code "141") (name "/P27") (class "Default")
      (node (ref "U6") (pin "8") (pinfunction "A7_8") (pintype "power_in"))
    )
    (net (code "142") (name "/P28") (class "Default")
      (node (ref "U6") (pin "9") (pinfunction "A8_9") (pintype "power_in"))
    )
    (net (code "143") (name "/P29") (class "Default")
      (node (ref "U10") (pin "1") (pinfunction "A1_1") (pintype "power_in"))
    )
    (net (code "144") (name "/P30") (class "Default")
      (node (ref "U10") (pin "3") (pinfunction "A2_3") (pintype "power_in"))
    )
    (net (code "145") (name "/P31") (class "Default")
      (node (ref "U10") (pin "4") (pinfunction "A3_4") (pintype "power_in"))
    )
    (net (code "146") (name "/P32") (class "Default")
      (node (ref "U10") (pin "5") (pinfunction "A4_5") (pintype "power_in"))
    )
    (net (code "147") (name "/P33") (class "Default")
      (node (ref "U10") (pin "6") (pinfunction "A5_6") (pintype "power_in"))
    )
    (net (code "148") (name "/P34") (class "Default")
      (node (ref "U10") (pin "8") (pinfunction "A7_8") (pintype "power_in"))
    )
    (net (code "149") (name "/P35") (class "Default")
      (node (ref "U10") (pin "9") (pinfunction "A8_9") (pintype "power_in"))
    )
    (net (code "150") (name "/P36") (class "Default")
      (node (ref "U11") (pin "1") (pinfunction "A1_1") (pintype "power_in"))
    )
    (net (code "151") (name "/P37") (class "Default")
      (node (ref "U11") (pin "4") (pinfunction "A3_4") (pintype "power_in"))
    )
    (net (code "152") (name "/P38") (class "Default")
      (node (ref "U11") (pin "5") (pinfunction "A4_5") (pintype "power_in"))
    )
    (net (code "153") (name "/P39") (class "Default")
      (node (ref "U11") (pin "6") (pinfunction "A5_6") (pintype "power_in"))
    )
    (net (code "154") (name "/P40") (class "Default")
      (node (ref "U11") (pin "7") (pinfunction "A6_7") (pintype "power_in"))
    )
    (net (code "155") (name "/P41") (class "Default")
      (node (ref "U14") (pin "1") (pinfunction "A1_1") (pintype "power_in"))
    )
    (net (code "156") (name "/P42") (class "Default")
      (node (ref "U14") (pin "3") (pinfunction "A2_3") (pintype "power_in"))
    )
    (net (code "157") (name "/P43") (class "Default")
      (node (ref "U14") (pin "6") (pinfunction "A5_6") (pintype "power_in"))
    )
    (net (code "158") (name "/P44") (class "Default")
      (node (ref "U14") (pin "7") (pinfunction "A6_7") (pintype "power_in"))
    )
    (net (code "159") (name "/P45") (class "Default")
      (node (ref "U14") (pin "8") (pinfunction "A7_8") (pintype "power_in"))
    )
    (net (code "160") (name "/P46") (class "Default")
      (node (ref "U14") (pin "9") (pinfunction "A8_9") (pintype "power_in"))
    )
    (net (code "161") (name "/P47") (class "Default")
      (node (ref "U15") (pin "1") (pinfunction "A1_1") (pintype "power_in"))
    )
    (net (code "162") (name "/P48") (class "Default")
      (node (ref "U15") (pin "3") (pinfunction "A2_3") (pintype "power_in"))
    )
    (net (code "163") (name "/P49") (class "Default")
      (node (ref "U15") (pin "5") (pinfunction "A4_5") (pintype "power_in"))
    )
    (net (code "164") (name "/P50") (class "Default")
      (node (ref "U15") (pin "6") (pinfunction "A5_6") (pintype "power_in"))
    )
    (net (code "165") (name "/P51") (class "Default")
      (node (ref "U15") (pin "7") (pinfunction "A6_7") (pintype "power_in"))
    )
    (net (code "166") (name "/P52") (class "Default")
      (node (ref "U15") (pin "9") (pinfunction "A8_9") (pintype "power_in"))
    )
    (net (code "167") (name "/P53") (class "Default")
      (node (ref "U16") (pin "1") (pinfunction "A1_1") (pintype "power_in"))
    )
    (net (code "168") (name "/P54") (class "Default")
      (node (ref "U16") (pin "3") (pinfunction "A2_3") (pintype "power_in"))
    )
    (net (code "169") (name "/P55") (class "Default")
      (node (ref "U16") (pin "4") (pinfunction "A3_4") (pintype "power_in"))
    )
    (net (code "170") (name "/P56") (class "Default")
      (node (ref "U16") (pin "5") (pinfunction "A4_5") (pintype "power_in"))
    )
    (net (code "171") (name "/P57") (class "Default")
      (node (ref "U16") (pin "6") (pinfunction "A5_6") (pintype "power_in"))
    )
    (net (code "172") (name "/P58") (class "Default")
      (node (ref "U16") (pin "7") (pinfunction "A6_7") (pintype "power_in"))
    )
    (net (code "173") (name "/P59") (class "Default")
      (node (ref "U20") (pin "1") (pinfunction "A1_1") (pintype "power_in"))
    )
    (net (code "174") (name "/P60") (class "Default")
      (node (ref "U20") (pin "3") (pinfunction "A2_3") (pintype "power_in"))
    )
    (net (code "175") (name "/P61") (class "Default")
      (node (ref "U20") (pin "4") (pinfunction "A3_4") (pintype "power_in"))
    )
    (net (code "176") (name "/P62") (class "Default")
      (node (ref "U20") (pin "5") (pinfunction "A4_5") (pintype "power_in"))
    )
    (net (code "177") (name "/RS485_N") (class "Default")
      (node (ref "J2") (pin "2") (pinfunction "2_2") (pintype "passive"))
      (node (ref "U22") (pin "6") (pinfunction "A/Y_6") (pintype "power_in"))
    )
    (net (code "178") (name "/RS485_P") (class "Default")
      (node (ref "J2") (pin "1") (pinfunction "1_1") (pintype "passive"))
      (node (ref "U22") (pin "7") (pinfunction "B/Z_7") (pintype "power_in"))
    )
    (net (code "179") (name "/RX_CHN_1") (class "Default")
      (node (ref "U11") (pin "3") (pinfunction "A2_3") (pintype "power_in"))
    )
    (net (code "180") (name "/RX_CHN_2") (class "Default")
      (node (ref "U15") (pin "8") (pinfunction "A7_8") (pintype "power_in"))
    )
    (net (code "181") (name "/RX_CHN_3") (class "Default")
      (node (ref "U22") (pin "1") (pinfunction "RO_1") (pintype "power_in"))
    )
    (net (code "182") (name "/SCL_CHN_1") (class "Default")
      (node (ref "U2") (pin "3") (pinfunction "A2_3") (pintype "power_in"))
    )
    (net (code "183") (name "/SCL_CHN_2") (class "Default")
      (node (ref "U2") (pin "5") (pinfunction "A4_5") (pintype "power_in"))
    )
    (net (code "184") (name "/SCL_CHN_3") (class "Default")
      (node (ref "U2") (pin "7") (pinfunction "A6_7") (pintype "power_in"))
    )
    (net (code "185") (name "/SCL_SENSORS") (class "Default")
      (node (ref "U1") (pin "4") (pinfunction "SCL_4") (pintype "power_in"))
      (node (ref "U12") (pin "4") (pinfunction "SCL_4") (pintype "power_in"))
      (node (ref "U13") (pin "4") (pinfunction "SCL_4") (pintype "power_in"))
      (node (ref "U18") (pin "4") (pinfunction "SCL_4") (pintype "power_in"))
      (node (ref "U19") (pin "1") (pinfunction "SCL_1") (pintype "power_in"))
      (node (ref "U2") (pin "14") (pinfunction "B6_14") (pintype "power_in"))
      (node (ref "U4") (pin "4") (pinfunction "SCL_4") (pintype "power_in"))
      (node (ref "U7") (pin "2") (pinfunction "A0_2") (pintype "power_in"))
      (node (ref "U7") (pin "4") (pinfunction "SCL_4") (pintype "power_in"))
      (node (ref "U9") (pin "4") (pinfunction "SCL_4") (pintype "power_in"))
    )
    (net (code "186") (name "/SDA_CHN_1") (class "Default")
      (node (ref "U2") (pin "1") (pinfunction "A1_1") (pintype "power_in"))
    )
    (net (code "187") (name "/SDA_CHN_2") (class "Default")
      (node (ref "U2") (pin "4") (pinfunction "A3_4") (pintype "power_in"))
    )
    (net (code "188") (name "/SDA_CHN_3") (class "Default")
      (node (ref "U2") (pin "6") (pinfunction "A5_6") (pintype "power_in"))
    )
    (net (code "189") (name "/SDA_SENSORS") (class "Default")
      (node (ref "U1") (pin "3") (pinfunction "SDA_3") (pintype "power_in"))
      (node (ref "U12") (pin "3") (pinfunction "SDA_3") (pintype "power_in"))
      (node (ref "U13") (pin "3") (pinfunction "SDA_3") (pintype "power_in"))
      (node (ref "U18") (pin "2") (pinfunction "A0_2") (pintype "power_in"))
      (node (ref "U18") (pin "3") (pinfunction "SDA_3") (pintype "power_in"))
      (node (ref "U19") (pin "6") (pinfunction "SDA_6") (pintype "power_in"))
      (node (ref "U2") (pin "15") (pinfunction "B5_15") (pintype "power_in"))
      (node (ref "U4") (pin "3") (pinfunction "SDA_3") (pintype "power_in"))
      (node (ref "U7") (pin "3") (pinfunction "SDA_3") (pintype "power_in"))
      (node (ref "U9") (pin "2") (pinfunction "A0_2") (pintype "power_in"))
      (node (ref "U9") (pin "3") (pinfunction "SDA_3") (pintype "power_in"))
    )
    (net (code "190") (name "/TX_CHN_1") (class "Default")
      (node (ref "U10") (pin "7") (pinfunction "A6_7") (pintype "power_in"))
    )
    (net (code "191") (name "/TX_CHN_2") (class "Default")
      (node (ref "U15") (pin "4") (pinfunction "A3_4") (pintype "power_in"))
    )
    (net (code "192") (name "/TX_CHN_3") (class "Default")
      (node (ref "U22") (pin "3") (pinfunction "DE_3") (pintype "power_in"))
    )
    (net (code "193") (name "/T{slash}R") (class "Default")
      (node (ref "U22") (pin "2") (pinfunction "~{RE}_2") (pintype "power_in"))
      (node (ref "U22") (pin "4") (pinfunction "DI_4") (pintype "power_in"))
    )
    (net (code "194") (name "/VCCA") (class "Default")
      (node (ref "U10") (pin "10") (pinfunction "OE_10") (pintype "power_in"))
      (node (ref "U10") (pin "2") (pinfunction "VCCA_2") (pintype "power_in"))
      (node (ref "U11") (pin "10") (pinfunction "OE_10") (pintype "power_in"))
      (node (ref "U11") (pin "2") (pinfunction "VCCA_2") (pintype "power_in"))
      (node (ref "U14") (pin "10") (pinfunction "OE_10") (pintype "power_in"))
      (node (ref "U14") (pin "2") (pinfunction "VCCA_2") (pintype "power_in"))
      (node (ref "U15") (pin "10") (pinfunction "OE_10") (pintype "power_in"))
      (node (ref "U15") (pin "2") (pinfunction "VCCA_2") (pintype "power_in"))
      (node (ref "U16") (pin "10") (pinfunction "OE_10") (pintype "power_in"))
      (node (ref "U16") (pin "2") (pinfunction "VCCA_2") (pintype "power_in"))
      (node (ref "U17") (pin "10") (pinfunction "OE_10") (pintype "power_in"))
      (node (ref "U17") (pin "2") (pinfunction "VCCA_2") (pintype "power_in"))
      (node (ref "U2") (pin "10") (pinfunction "OE_10") (pintype "power_in"))
      (node (ref "U2") (pin "2") (pinfunction "VCCA_2") (pintype "power_in"))
      (node (ref "U20") (pin "10") (pinfunction "OE_10") (pintype "power_in"))
      (node (ref "U20") (pin "2") (pinfunction "VCCA_2") (pintype "power_in"))
      (node (ref "U3") (pin "10") (pinfunction "OE_10") (pintype "power_in"))
      (node (ref "U3") (pin "2") (pinfunction "VCCA_2") (pintype "power_in"))
      (node (ref "U5") (pin "10") (pinfunction "OE_10") (pintype "power_in"))
      (node (ref "U5") (pin "2") (pinfunction "VCCA_2") (pintype "power_in"))
      (node (ref "U6") (pin "10") (pinfunction "OE_10") (pintype "power_in"))
      (node (ref "U6") (pin "2") (pinfunction "VCCA_2") (pintype "power_in"))
      (node (ref "U8") (pin "10") (pinfunction "OE_10") (pintype "power_in"))
      (node (ref "U8") (pin "2") (pinfunction "VCCA_2") (pintype "power_in"))
    )
    (net (code "195") (name "/VCCB") (class "Default")
      (node (ref "U10") (pin "19") (pinfunction "VCCB_19") (pintype "power_in"))
      (node (ref "U11") (pin "19") (pinfunction "VCCB_19") (pintype "power_in"))
      (node (ref "U14") (pin "19") (pinfunction "VCCB_19") (pintype "power_in"))
      (node (ref "U15") (pin "19") (pinfunction "VCCB_19") (pintype "power_in"))
      (node (ref "U16") (pin "19") (pinfunction "VCCB_19") (pintype "power_in"))
      (node (ref "U17") (pin "19") (pinfunction "VCCB_19") (pintype "power_in"))
      (node (ref "U2") (pin "19") (pinfunction "VCCB_19") (pintype "power_in"))
      (node (ref "U20") (pin "19") (pinfunction "VCCB_19") (pintype "power_in"))
      (node (ref "U3") (pin "19") (pinfunction "VCCB_19") (pintype "power_in"))
      (node (ref "U5") (pin "19") (pinfunction "VCCB_19") (pintype "power_in"))
      (node (ref "U6") (pin "19") (pinfunction "VCCB_19") (pintype "power_in"))
      (node (ref "U8") (pin "19") (pinfunction "VCCB_19") (pintype "power_in"))
    )
    (net (code "196") (name "/VS") (class "Default")
      (node (ref "U1") (pin "5") (pinfunction "VS_5") (pintype "power_in"))
      (node (ref "U12") (pin "1") (pinfunction "A1_1") (pintype "power_in"))
      (node (ref "U12") (pin "5") (pinfunction "VS_5") (pintype "power_in"))
      (node (ref "U13") (pin "1") (pinfunction "A1_1") (pintype "power_in"))
      (node (ref "U13") (pin "2") (pinfunction "A0_2") (pintype "power_in"))
      (node (ref "U13") (pin "5") (pinfunction "VS_5") (pintype "power_in"))
      (node (ref "U18") (pin "1") (pinfunction "A1_1") (pintype "power_in"))
      (node (ref "U18") (pin "5") (pinfunction "VS_5") (pintype "power_in"))
      (node (ref "U19") (pin "5") (pinfunction "V+_5") (pintype "power_in"))
      (node (ref "U21") (pin "2") (pinfunction "VDD_1_2") (pintype "power_in"))
      (node (ref "U21") (pin "4") (pinfunction "VDD_2_4") (pintype "power_in"))
      (node (ref "U21") (pin "42") (pinfunction "~{RESET}_42") (pintype "power_in"))
      (node (ref "U21") (pin "45") (pinfunction "VDD_5_45") (pintype "power_in"))
      (node (ref "U21") (pin "6") (pinfunction "VDD_3_6") (pintype "power_in"))
      (node (ref "U21") (pin "8") (pinfunction "VDD_4_8") (pintype "power_in"))
      (node (ref "U22") (pin "8") (pinfunction "VCC_8") (pintype "power_in"))
      (node (ref "U4") (pin "2") (pinfunction "A0_2") (pintype "power_in"))
      (node (ref "U4") (pin "5") (pinfunction "VS_5") (pintype "power_in"))
      (node (ref "U7") (pin "5") (pinfunction "VS_5") (pintype "power_in"))
      (node (ref "U9") (pin "5") (pinfunction "VS_5") (pintype "power_in"))
    )
    (net (code "197") (name "GND") (class "Default")
      (node (ref "C14") (pin "2") (pinfunction "2_2") (pintype "passive"))
      (node (ref "C15") (pin "2") (pinfunction "2_2") (pintype "passive"))
      (node (ref "C17") (pin "2") (pinfunction "2_2") (pintype "passive"))
      (node (ref "C18") (pin "2") (pinfunction "2_2") (pintype "passive"))
      (node (ref "C19") (pin "1") (pinfunction "1_1") (pintype "passive"))
      (node (ref "C20") (pin "1") (pinfunction "1_1") (pintype "passive"))
      (node (ref "C21") (pin "1") (pinfunction "1_1") (pintype "passive"))
      (node (ref "C22") (pin "1") (pinfunction "1_1") (pintype "passive"))
      (node (ref "C23") (pin "1") (pinfunction "1_1") (pintype "passive"))
      (node (ref "C24") (pin "1") (pinfunction "1_1") (pintype "passive"))
      (node (ref "C25") (pin "1") (pinfunction "1_1") (pintype "passive"))
      (node (ref "C26") (pin "1") (pinfunction "1_1") (pintype "passive"))
      (node (ref "C27") (pin "1") (pinfunction "1_1") (pintype "passive"))
      (node (ref "C28") (pin "1") (pinfunction "1_1") (pintype "passive"))
      (node (ref "J5") (pin "10") (pinfunction "10_10") (pintype "passive"))
      (node (ref "J5") (pin "2") (pinfunction "2_2") (pintype "passive"))
      (node (ref "J5") (pin "4") (pinfunction "4_4") (pintype "passive"))
      (node (ref "J5") (pin "6") (pinfunction "6_6") (pintype "passive"))
      (node (ref "J5") (pin "8") (pinfunction "8_8") (pintype "passive"))
      (node (ref "J6") (pin "10") (pinfunction "10_10") (pintype "passive"))
      (node (ref "J6") (pin "2") (pinfunction "2_2") (pintype "passive"))
      (node (ref "J6") (pin "4") (pinfunction "4_4") (pintype "passive"))
      (node (ref "J6") (pin "6") (pinfunction "6_6") (pintype "passive"))
      (node (ref "J6") (pin "8") (pinfunction "8_8") (pintype "passive"))
      (node (ref "U1") (pin "1") (pinfunction "A1_1") (pintype "power_in"))
      (node (ref "U1") (pin "2") (pinfunction "A0_2") (pintype "power_in"))
      (node (ref "U1") (pin "6") (pinfunction "GND_6") (pintype "power_in"))
      (node (ref "U10") (pin "11") (pinfunction "GND_11") (pintype "power_in"))
      (node (ref "U11") (pin "11") (pinfunction "GND_11") (pintype "power_in"))
      (node (ref "U12") (pin "2") (pinfunction "A0_2") (pintype "power_in"))
      (node (ref "U12") (pin "6") (pinfunction "GND_6") (pintype "power_in"))
      (node (ref "U13") (pin "6") (pinfunction "GND_6") (pintype "power_in"))
      (node (ref "U14") (pin "11") (pinfunction "GND_11") (pintype "power_in"))
      (node (ref "U15") (pin "11") (pinfunction "GND_11") (pintype "power_in"))
      (node (ref "U16") (pin "11") (pinfunction "GND_11") (pintype "power_in"))
      (node (ref "U17") (pin "11") (pinfunction "GND_11") (pintype "power_in"))
      (node (ref "U18") (pin "6") (pinfunction "GND_6") (pintype "power_in"))
      (node (ref "U19") (pin "2") (pinfunction "GND_2") (pintype "power_in"))
      (node (ref "U19") (pin "4") (pinfunction "ADD0_4") (pintype "power_in"))
      (node (ref "U2") (pin "11") (pinfunction "GND_11") (pintype "power_in"))
      (node (ref "U20") (pin "11") (pinfunction "GND_11") (pintype "power_in"))
      (node (ref "U21") (pin "1") (pinfunction "GND_1_1") (pintype "power_in"))
      (node (ref "U21") (pin "12") (pinfunction "GND_6_12") (pintype "power_in"))
      (node (ref "U21") (pin "15") (pinfunction "GND_7_15") (pintype "power_in"))
      (node (ref "U21") (pin "17") (pinfunction "CH2_17") (pintype "power_in"))
      (node (ref "U21") (pin "19") (pinfunction "CH4_19") (pintype "power_in"))
      (node (ref "U21") (pin "21") (pinfunction "CH6_21") (pintype "power_in"))
      (node (ref "U21") (pin "23") (pinfunction "CH8_23") (pintype "power_in"))
      (node (ref "U21") (pin "25") (pinfunction "CH10_25") (pintype "power_in"))
      (node (ref "U21") (pin "27") (pinfunction "CH12_27") (pintype "power_in"))
      (node (ref "U21") (pin "29") (pinfunction "CH14_29") (pintype "power_in"))
      (node (ref "U21") (pin "3") (pinfunction "GND_2_3") (pintype "power_in"))
      (node (ref "U21") (pin "31") (pinfunction "CH16_31") (pintype "power_in"))
      (node (ref "U21") (pin "33") (pinfunction "CH18_33") (pintype "power_in"))
      (node (ref "U21") (pin "35") (pinfunction "CH20_35") (pintype "power_in"))
      (node (ref "U21") (pin "36") (pinfunction "COM_36") (pintype "power_in"))
      (node (ref "U21") (pin "44") (pinfunction "GND_8_44") (pintype "power_in"))
      (node (ref "U21") (pin "5") (pinfunction "GND_3_5") (pintype "power_in"))
      (node (ref "U21") (pin "7") (pinfunction "GND_4_7") (pintype "power_in"))
      (node (ref "U21") (pin "9") (pinfunction "GND_5_9") (pintype "power_in"))
      (node (ref "U22") (pin "5") (pinfunction "GND_5") (pintype "power_in"))
      (node (ref "U3") (pin "11") (pinfunction "GND_11") (pintype "power_in"))
      (node (ref "U4") (pin "1") (pinfunction "A1_1") (pintype "power_in"))
      (node (ref "U4") (pin "6") (pinfunction "GND_6") (pintype "power_in"))
      (node (ref "U5") (pin "11") (pinfunction "GND_11") (pintype "power_in"))
      (node (ref "U6") (pin "11") (pinfunction "GND_11") (pintype "power_in"))
      (node (ref "U7") (pin "1") (pinfunction "A1_1") (pintype "power_in"))
      (node (ref "U7") (pin "6") (pinfunction "GND_6") (pintype "power_in"))
      (node (ref "U8") (pin "11") (pinfunction "GND_11") (pintype "power_in"))
      (node (ref "U9") (pin "1") (pinfunction "A1_1") (pintype "power_in"))
      (node (ref "U9") (pin "6") (pinfunction "GND_6") (pintype "power_in"))
    )
    (net (code "198") (name "Net-(U21-INTERRUPT)") (class "Default")
      (node (ref "CN14") (pin "1") (pinfunction "1_1") (pintype "passive"))
      (node (ref "U21") (pin "37") (pinfunction "INTERRUPT_37") (pintype "power_in"))
    )
    (net (code "199") (name "Net-(U21-LDO)") (class "Default")
      (node (ref "C18") (pin "1") (pinfunction "1_1") (pintype "passive"))
      (node (ref "U21") (pin "43") (pinfunction "LDO_43") (pintype "power_in"))
    )
    (net (code "200") (name "Net-(U21-Q1)") (class "Default")
      (node (ref "C16") (pin "1") (pinfunction "1_1") (pintype "passive"))
      (node (ref "U21") (pin "48") (pinfunction "Q1_48") (pintype "power_in"))
    )
    (net (code "201") (name "Net-(U21-Q2)") (class "Default")
      (node (ref "C16") (pin "2") (pinfunction "2_2") (pintype "passive"))
      (node (ref "U21") (pin "47") (pinfunction "Q2_47") (pintype "power_in"))
    )
    (net (code "202") (name "Net-(U21-Q3)") (class "Default")
      (node (ref "C17") (pin "1") (pinfunction "1_1") (pintype "passive"))
      (node (ref "U21") (pin "46") (pinfunction "Q3_46") (pintype "power_in"))
    )
    (net (code "203") (name "Net-(U21-VREFOUT)") (class "Default")
      (node (ref "C14") (pin "1") (pinfunction "1_1") (pintype "passive"))
      (node (ref "U21") (pin "13") (pinfunction "VREFOUT_13") (pintype "power_in"))
      (node (ref "U21") (pin "14") (pinfunction "VREFP_14") (pintype "power_in"))
    )
    (net (code "204") (name "Net-(U21-VREF_BYP)") (class "Default")
      (node (ref "C15") (pin "1") (pinfunction "1_1") (pintype "passive"))
      (node (ref "U21") (pin "11") (pinfunction "VREF_BYP_11") (pintype "power_in"))
    )
    (net (code "205") (name "unconnected-(U2-A7-Pad8)") (class "Default")
      (node (ref "U2") (pin "8") (pinfunction "A7_8") (pintype "power_in+no_connect"))
    )
    (net (code "206") (name "unconnected-(U2-A8-Pad9)") (class "Default")
      (node (ref "U2") (pin "9") (pinfunction "A8_9") (pintype "power_in+no_connect"))
    )
    (net (code "207") (name "unconnected-(U2-B7-Pad13)") (class "Default")
      (node (ref "U2") (pin "13") (pinfunction "B7_13") (pintype "power_in+no_connect"))
    )
    (net (code "208") (name "unconnected-(U2-B8-Pad12)") (class "Default")
      (node (ref "U2") (pin "12") (pinfunction "B8_12") (pintype "power_in+no_connect"))
    )
    (net (code "209") (name "unconnected-(U16-A7-Pad8)") (class "Default")
      (node (ref "U16") (pin "8") (pinfunction "A7_8") (pintype "power_in+no_connect"))
    )
    (net (code "210") (name "unconnected-(U16-A8-Pad9)") (class "Default")
      (node (ref "U16") (pin "9") (pinfunction "A8_9") (pintype "power_in+no_connect"))
    )
    (net (code "211") (name "unconnected-(U16-B7-Pad13)") (class "Default")
      (node (ref "U16") (pin "13") (pinfunction "B7_13") (pintype "power_in+no_connect"))
    )
    (net (code "212") (name "unconnected-(U16-B8-Pad12)") (class "Default")
      (node (ref "U16") (pin "12") (pinfunction "B8_12") (pintype "power_in+no_connect"))
    )
    (net (code "213") (name "unconnected-(U17-A5-Pad6)") (class "Default")
      (node (ref "U17") (pin "6") (pinfunction "A5_6") (pintype "power_in+no_connect"))
    )
    (net (code "214") (name "unconnected-(U17-A6-Pad7)") (class "Default")
      (node (ref "U17") (pin "7") (pinfunction "A6_7") (pintype "power_in+no_connect"))
    )
    (net (code "215") (name "unconnected-(U17-A7-Pad8)") (class "Default")
      (node (ref "U17") (pin "8") (pinfunction "A7_8") (pintype "power_in+no_connect"))
    )
    (net (code "216") (name "unconnected-(U17-A8-Pad9)") (class "Default")
      (node (ref "U17") (pin "9") (pinfunction "A8_9") (pintype "power_in+no_connect"))
    )
    (net (code "217") (name "unconnected-(U17-B5-Pad15)") (class "Default")
      (node (ref "U17") (pin "15") (pinfunction "B5_15") (pintype "power_in+no_connect"))
    )
    (net (code "218") (name "unconnected-(U17-B6-Pad14)") (class "Default")
      (node (ref "U17") (pin "14") (pinfunction "B6_14") (pintype "power_in+no_connect"))
    )
    (net (code "219") (name "unconnected-(U17-B7-Pad13)") (class "Default")
      (node (ref "U17") (pin "13") (pinfunction "B7_13") (pintype "power_in+no_connect"))
    )
    (net (code "220") (name "unconnected-(U17-B8-Pad12)") (class "Default")
      (node (ref "U17") (pin "12") (pinfunction "B8_12") (pintype "power_in+no_connect"))
    )
    (net (code "221") (name "unconnected-(U19-ALERT-Pad3)") (class "Default")
      (node (ref "U19") (pin "3") (pinfunction "ALERT_3") (pintype "power_in+no_connect"))
    )
    (net (code "222") (name "unconnected-(U20-A5-Pad6)") (class "Default")
      (node (ref "U20") (pin "6") (pinfunction "A5_6") (pintype "power_in+no_connect"))
    )
    (net (code "223") (name "unconnected-(U20-A6-Pad7)") (class "Default")
      (node (ref "U20") (pin "7") (pinfunction "A6_7") (pintype "power_in+no_connect"))
    )
    (net (code "224") (name "unconnected-(U20-A7-Pad8)") (class "Default")
      (node (ref "U20") (pin "8") (pinfunction "A7_8") (pintype "power_in+no_connect"))
    )
    (net (code "225") (name "unconnected-(U20-A8-Pad9)") (class "Default")
      (node (ref "U20") (pin "9") (pinfunction "A8_9") (pintype "power_in+no_connect"))
    )
    (net (code "226") (name "unconnected-(U20-B5-Pad15)") (class "Default")
      (node (ref "U20") (pin "15") (pinfunction "B5_15") (pintype "power_in+no_connect"))
    )
    (net (code "227") (name "unconnected-(U20-B6-Pad14)") (class "Default")
      (node (ref "U20") (pin "14") (pinfunction "B6_14") (pintype "power_in+no_connect"))
    )
    (net (code "228") (name "unconnected-(U20-B7-Pad13)") (class "Default")
      (node (ref "U20") (pin "13") (pinfunction "B7_13") (pintype "power_in+no_connect"))
    )
    (net (code "229") (name "unconnected-(U20-B8-Pad12)") (class "Default")
      (node (ref "U20") (pin "12") (pinfunction "B8_12") (pintype "power_in+no_connect"))
    )
  )
)
